# ta_-sch_ma-oprava.net
KiCad netlist of a schematic drawn in EAGLE
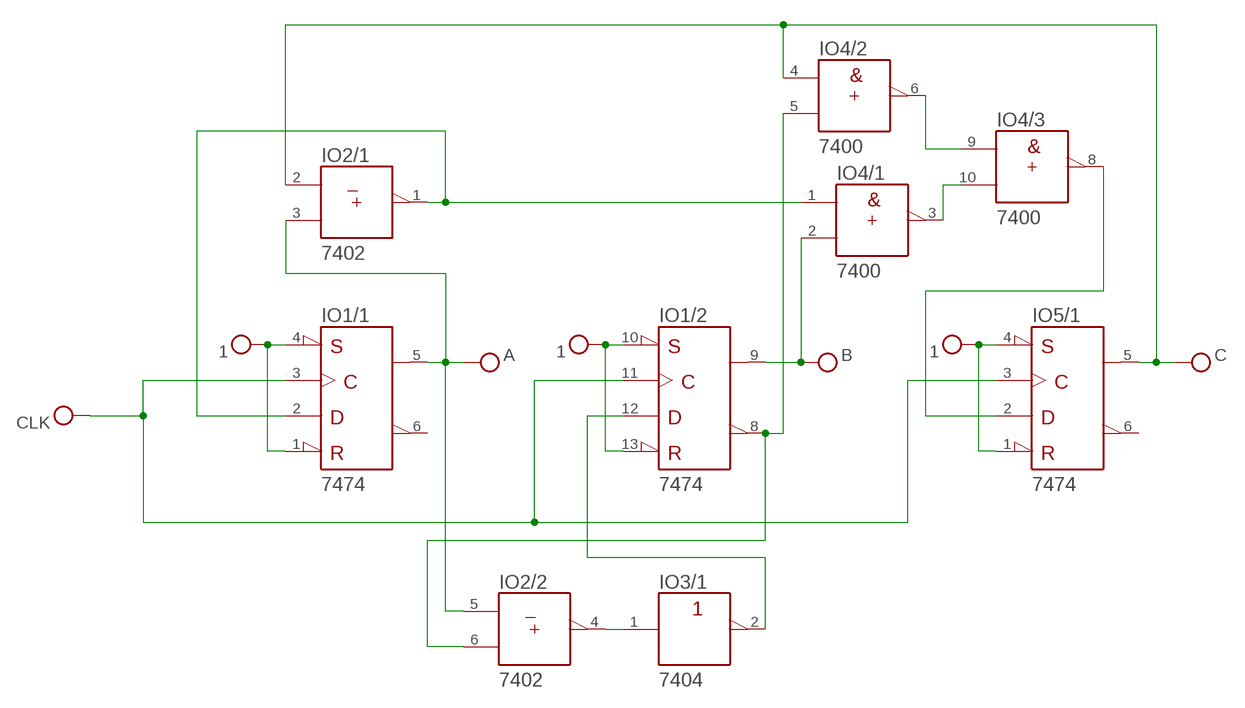
[diagram p0: schematic, sheet 1]

(export (version "E")
  (design (tool "Eeschema 10.0.6"))
  (components
    (comp (ref "IO1")
      (value "7474")
      (footprint "eagle-import:DIL14")
      (libsource (lib "eagle-import") (part "7474N"))
    )
    (comp (ref "IO2")
      (value "7402")
      (footprint "eagle-import:DIL14")
      (libsource (lib "eagle-import") (part "7402N"))
    )
    (comp (ref "IO3")
      (value "7404")
      (footprint "eagle-import:DIL14")
      (libsource (lib "eagle-import") (part "7404N"))
    )
    (comp (ref "IO4")
      (value "7400")
      (footprint "eagle-import:DIL14")
      (libsource (lib "eagle-import") (part "7400N"))
    )
    (comp (ref "IO5")
      (value "7474")
      (footprint "eagle-import:DIL14")
      (libsource (lib "eagle-import") (part "7474N"))
    )
  )
  (nets
    (net (code "1") (name "1") (class "Default")
      (node (ref "IO1") (pin "1") (pinfunction "~{CLR}_1") (pintype "input"))
      (node (ref "IO1") (pin "10") (pinfunction "~{PRE}_10") (pintype "input"))
      (node (ref "IO1") (pin "11") (pinfunction "CLK_11") (pintype "input"))
      (node (ref "IO1") (pin "13") (pinfunction "~{CLR}_13") (pintype "input"))
      (node (ref "IO1") (pin "3") (pinfunction "CLK_3") (pintype "input"))
      (node (ref "IO1") (pin "4") (pinfunction "~{PRE}_4") (pintype "input"))
      (node (ref "IO1") (pin "5") (pinfunction "Q_5") (pintype "output"))
      (node (ref "IO1") (pin "9") (pinfunction "Q_9") (pintype "output"))
      (node (ref "IO2") (pin "2") (pinfunction "A_2") (pintype "input"))
      (node (ref "IO2") (pin "3") (pinfunction "B_3") (pintype "input"))
      (node (ref "IO2") (pin "5") (pinfunction "A_5") (pintype "input"))
      (node (ref "IO4") (pin "2") (pinfunction "B_2") (pintype "input"))
      (node (ref "IO4") (pin "4") (pinfunction "A_4") (pintype "input"))
      (node (ref "IO5") (pin "1") (pinfunction "~{CLR}_1") (pintype "input"))
      (node (ref "IO5") (pin "3") (pinfunction "CLK_3") (pintype "input"))
      (node (ref "IO5") (pin "4") (pinfunction "~{PRE}_4") (pintype "input"))
      (node (ref "IO5") (pin "5") (pinfunction "Q_5") (pintype "output"))
    )
    (net (code "2") (name "Net-(IO1C-D)") (class "Default")
      (node (ref "IO1") (pin "2") (pinfunction "D_2") (pintype "input"))
      (node (ref "IO2") (pin "1") (pinfunction "Y_1") (pintype "output"))
      (node (ref "IO4") (pin "1") (pinfunction "A_1") (pintype "input"))
    )
    (net (code "3") (name "Net-(IO1D-D)") (class "Default")
      (node (ref "IO1") (pin "12") (pinfunction "D_12") (pintype "input"))
      (node (ref "IO3") (pin "2") (pinfunction "Y_2") (pintype "output"))
    )
    (net (code "4") (name "Net-(IO1D-~{Q})") (class "Default")
      (node (ref "IO1") (pin "8") (pinfunction "~{Q}_8") (pintype "output"))
      (node (ref "IO2") (pin "6") (pinfunction "B_6") (pintype "input"))
      (node (ref "IO4") (pin "5") (pinfunction "B_5") (pintype "input"))
    )
    (net (code "5") (name "Net-(IO2D-Y)") (class "Default")
      (node (ref "IO2") (pin "4") (pinfunction "Y_4") (pintype "output"))
      (node (ref "IO3") (pin "1") (pinfunction "A_1") (pintype "input"))
    )
    (net (code "6") (name "Net-(IO4C-Y)") (class "Default")
      (node (ref "IO4") (pin "10") (pinfunction "B_10") (pintype "input"))
      (node (ref "IO4") (pin "3") (pinfunction "Y_3") (pintype "output"))
    )
    (net (code "7") (name "Net-(IO4D-Y)") (class "Default")
      (node (ref "IO4") (pin "6") (pinfunction "Y_6") (pintype "output"))
      (node (ref "IO4") (pin "9") (pinfunction "A_9") (pintype "input"))
    )
    (net (code "8") (name "Net-(IO4E-Y)") (class "Default")
      (node (ref "IO4") (pin "8") (pinfunction "Y_8") (pintype "output"))
      (node (ref "IO5") (pin "2") (pinfunction "D_2") (pintype "input"))
    )
    (net (code "9") (name "unconnected-(IO1C-~{Q}-Pad6)") (class "Default")
      (node (ref "IO1") (pin "6") (pinfunction "~{Q}_6") (pintype "output"))
    )
    (net (code "10") (name "unconnected-(IO5C-~{Q}-Pad6)") (class "Default")
      (node (ref "IO5") (pin "6") (pinfunction "~{Q}_6") (pintype "output"))
    )
  )
)
